# altium_sample_lf.net
KiCad netlist of a schematic drawn in Altium Designer
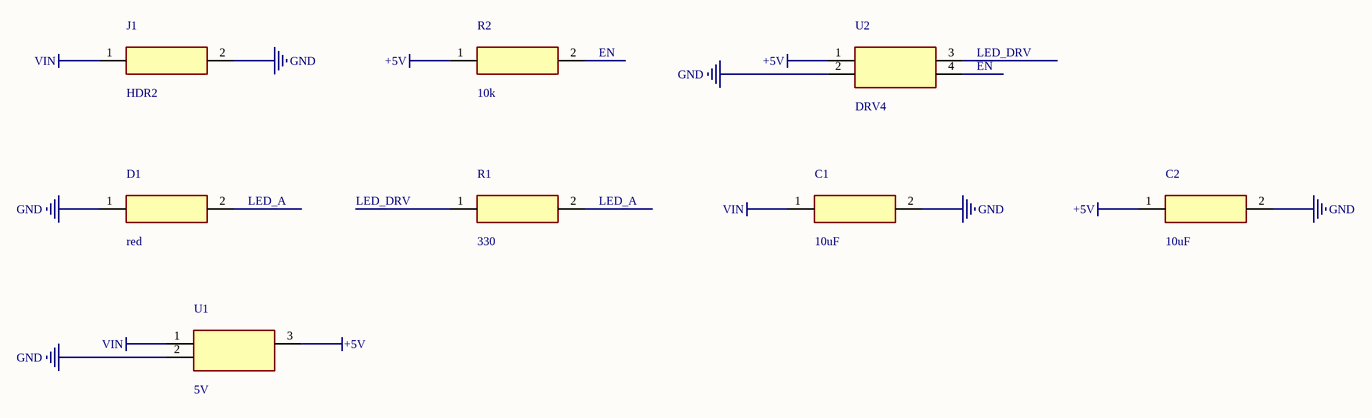
[diagram p0: altium_sample_lf.SchDoc]

(export (version "E")
  (design (tool "Eeschema 10.0.6"))
  (components
    (comp (ref "C1")
      (value "10uF")
      (footprint "FenoliteSample:C0603")
      (libsource (lib "FenoliteSample") (part "CAP"))
    )
    (comp (ref "C2")
      (value "10uF")
      (footprint "FenoliteSample:C0603")
      (libsource (lib "FenoliteSample") (part "CAP"))
    )
    (comp (ref "D1")
      (value "red")
      (footprint "FenoliteSample:LED0603")
      (libsource (lib "FenoliteSample") (part "LED"))
    )
    (comp (ref "J1")
      (value "HDR2")
      (footprint "FenoliteSample:HDR1X2")
      (libsource (lib "FenoliteSample") (part "HDR2"))
    )
    (comp (ref "R1")
      (value "330")
      (footprint "FenoliteSample:R0603")
      (libsource (lib "FenoliteSample") (part "RES"))
    )
    (comp (ref "R2")
      (value "10k")
      (footprint "FenoliteSample:R0603")
      (libsource (lib "FenoliteSample") (part "RES"))
    )
    (comp (ref "U1")
      (value "5V")
      (footprint "FenoliteSample:SOT23")
      (libsource (lib "FenoliteSample") (part "LDO3"))
    )
    (comp (ref "U2")
      (value "DRV4")
      (footprint "FenoliteSample:SOT143")
      (libsource (lib "FenoliteSample") (part "DRV4"))
    )
  )
  (nets
    (net (code "1") (name "+5V") (class "Default")
      (node (ref "C2") (pin "1") (pinfunction "1_1") (pintype "passive"))
      (node (ref "R2") (pin "1") (pinfunction "1_1") (pintype "passive"))
      (node (ref "U1") (pin "3") (pinfunction "3_3") (pintype "passive"))
      (node (ref "U2") (pin "1") (pinfunction "1_1") (pintype "passive"))
    )
    (net (code "2") (name "/EN") (class "Default")
      (node (ref "R2") (pin "2") (pinfunction "2_2") (pintype "passive"))
      (node (ref "U2") (pin "4") (pinfunction "4_4") (pintype "passive"))
    )
    (net (code "3") (name "/LED_A") (class "Default")
      (node (ref "D1") (pin "2") (pinfunction "2_2") (pintype "passive"))
      (node (ref "R1") (pin "2") (pinfunction "2_2") (pintype "passive"))
    )
    (net (code "4") (name "/LED_DRV") (class "Default")
      (node (ref "R1") (pin "1") (pinfunction "1_1") (pintype "passive"))
      (node (ref "U2") (pin "3") (pinfunction "3_3") (pintype "passive"))
    )
    (net (code "5") (name "GND") (class "Default")
      (node (ref "C1") (pin "2") (pinfunction "2_2") (pintype "passive"))
      (node (ref "C2") (pin "2") (pinfunction "2_2") (pintype "passive"))
      (node (ref "D1") (pin "1") (pinfunction "1_1") (pintype "passive"))
      (node (ref "J1") (pin "2") (pinfunction "2_2") (pintype "passive"))
      (node (ref "U1") (pin "2") (pinfunction "2_2") (pintype "passive"))
      (node (ref "U2") (pin "2") (pinfunction "2_2") (pintype "passive"))
    )
    (net (code "6") (name "VIN") (class "Default")
      (node (ref "C1") (pin "1") (pinfunction "1_1") (pintype "passive"))
      (node (ref "J1") (pin "1") (pinfunction "1_1") (pintype "passive"))
      (node (ref "U1") (pin "1") (pinfunction "1_1") (pintype "passive"))
    )
  )
)
